# EMG.net
KiCad netlist of a schematic drawn in Altium Designer
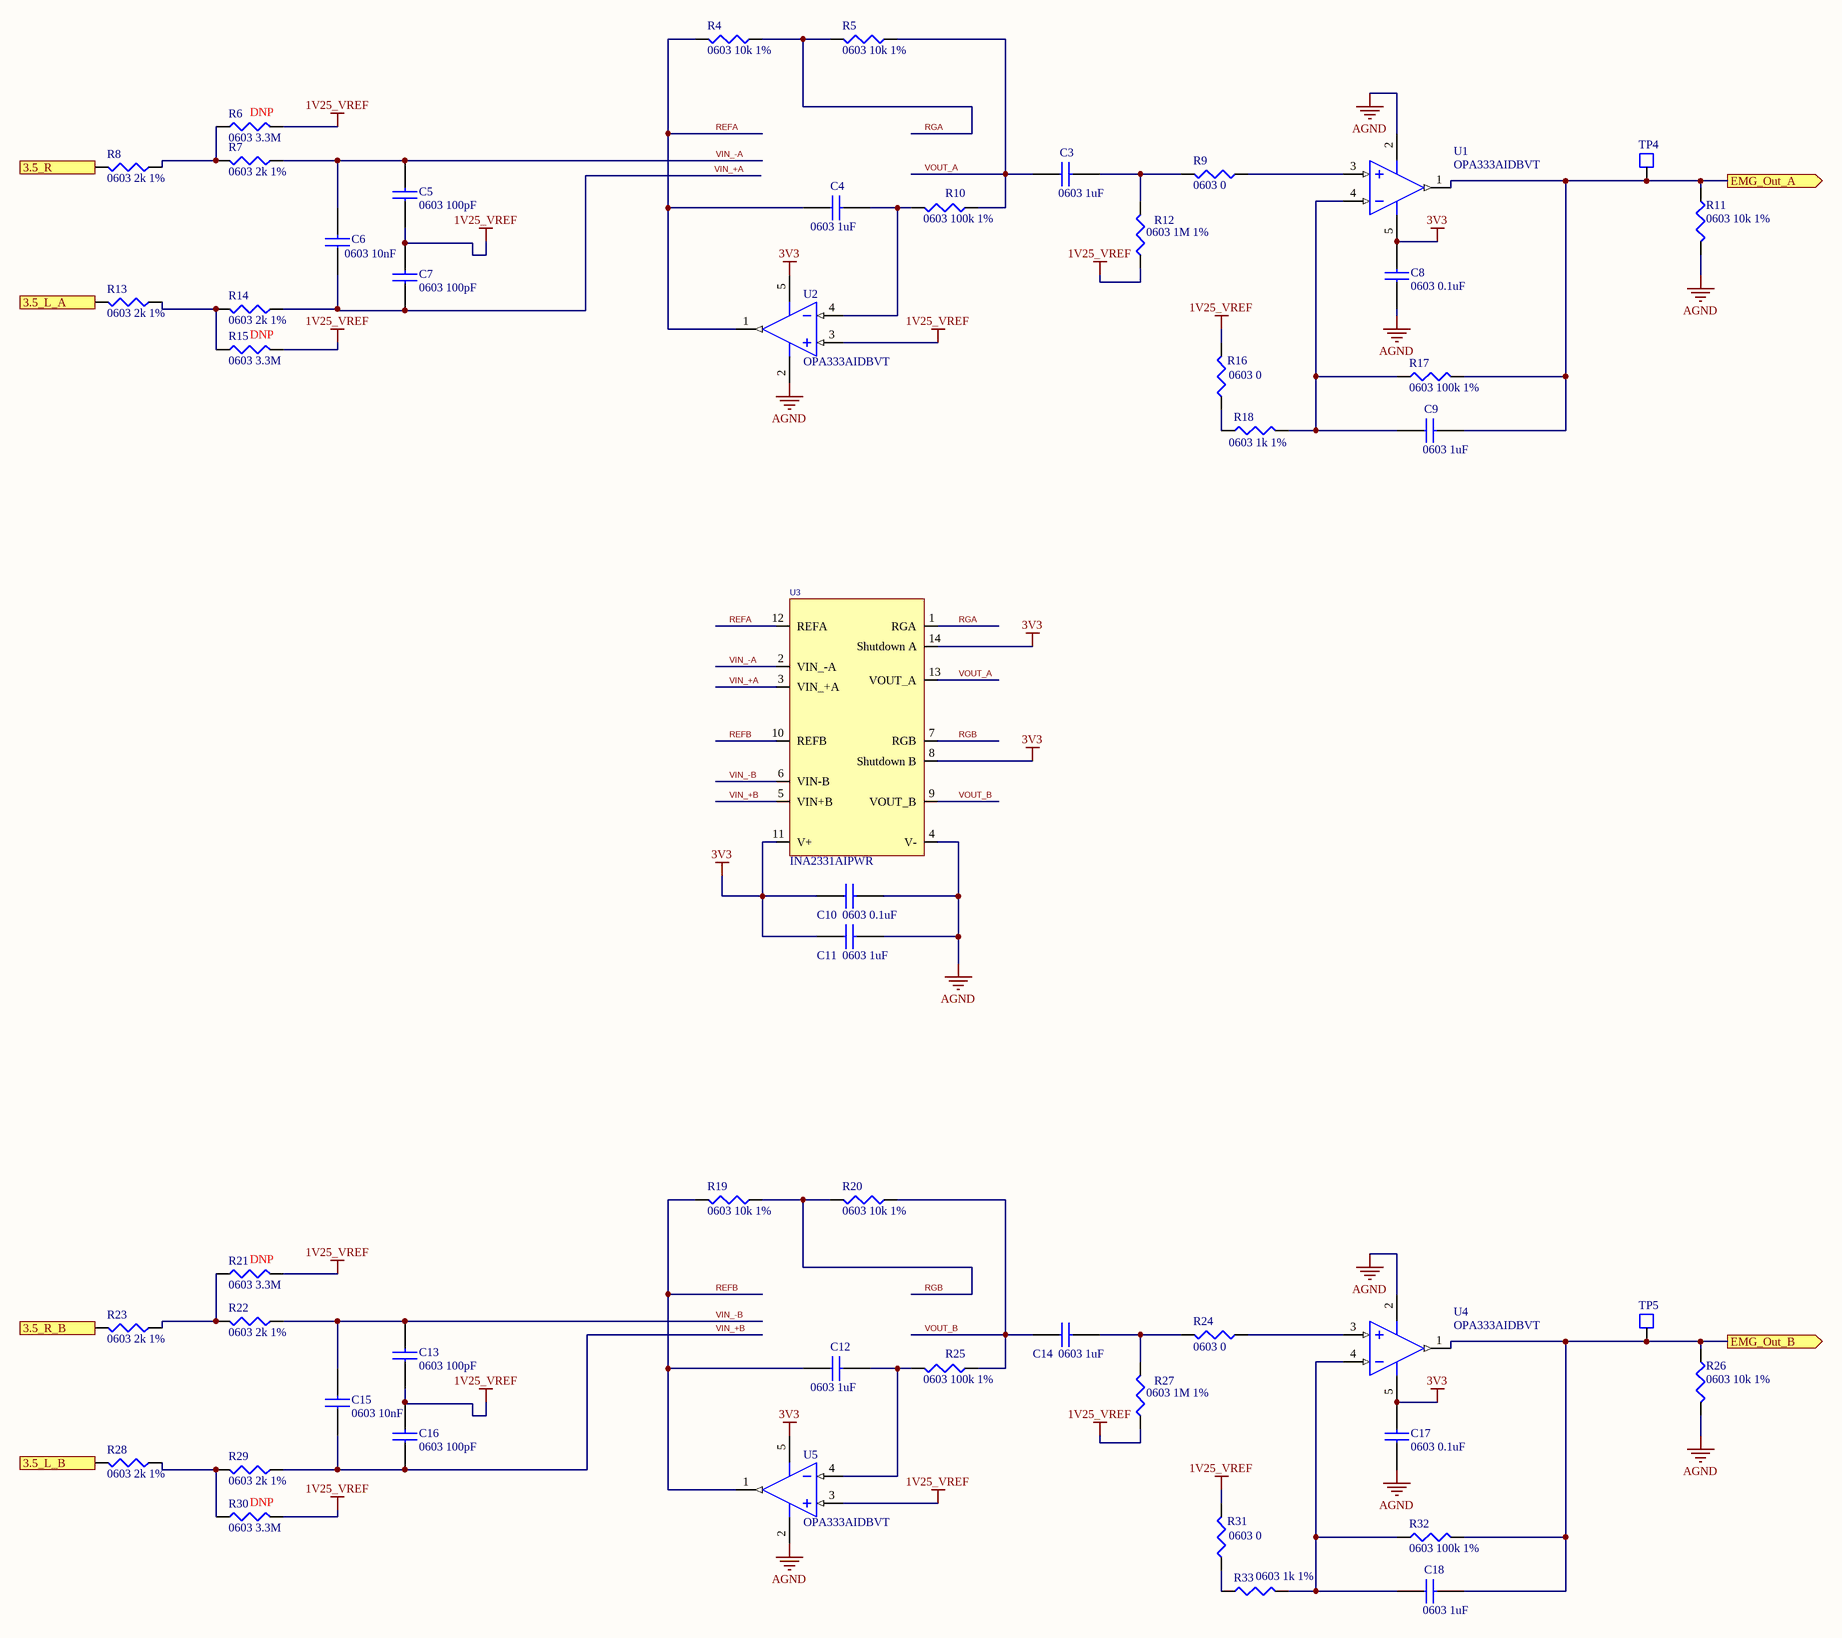
[diagram p0: EMG.SchDoc]

(export (version "E")
  (design (tool "Eeschema 10.0.6"))
  (components
    (comp (ref "C3")
      (value "0603 1uF")
      (footprint "CAP_0603_CER")
      (description "Generic Cap for NC (No Polar)\r\nESR <30mOhm\r\nESL <1.5nH,\r\nX5R")
      (fields
        (field (name "MANUFACTURER") "KEMET")
        (field (name "MANUFACTURER PART NUMBER") "C0603C105K8RAC7867")
      )
      (libsource (lib "BioSens") (part "CAP_NP"))
    )
    (comp (ref "C4")
      (value "0603 1uF")
      (footprint "CAP_0603_CER")
      (description "Generic Cap for NC (No Polar)\r\nESR <30mOhm\r\nESL <1.5nH,\r\nX5R")
      (fields
        (field (name "MANUFACTURER") "KEMET")
        (field (name "MANUFACTURER PART NUMBER") "C0603C105K8RAC7867")
      )
      (libsource (lib "BioSens") (part "CAP_NP"))
    )
    (comp (ref "C5")
      (value "0603 100pF")
      (footprint "CAP_0603_CER")
      (description "Generic Cap for NC (No Polar)\r\nESR <30mOhm\r\nESL <1.5nH,\r\nC0G")
      (fields
        (field (name "MANUFACTURER") "KEMET")
        (field (name "MANUFACTURER PART NUMBER") "C0603C101J3GAC7867")
      )
      (libsource (lib "BioSens") (part "CAP_NP"))
    )
    (comp (ref "C6")
      (value "0603 10nF")
      (footprint "CAP_0603_CER")
      (description "Generic Cap for NC (No Polar)\r\nESR <30mOhm\r\nESL <1.5nH,\r\nX7R")
      (fields
        (field (name "MANUFACTURER") "KEMET")
        (field (name "MANUFACTURER PART NUMBER") "C0603C103K4REC7867")
      )
      (libsource (lib "BioSens") (part "CAP_NP"))
    )
    (comp (ref "C7")
      (value "0603 100pF")
      (footprint "CAP_0603_CER")
      (description "Generic Cap for NC (No Polar)\r\nESR <30mOhm\r\nESL <1.5nH,\r\nC0G")
      (fields
        (field (name "MANUFACTURER") "KEMET")
        (field (name "MANUFACTURER PART NUMBER") "C0603C101J3GAC7867")
      )
      (libsource (lib "BioSens") (part "CAP_NP"))
    )
    (comp (ref "C8")
      (value "0603 0.1uF")
      (footprint "CAP_0603_CER")
      (description "Generic Cap for NC (No Polar)\r\nESR <30mOhm\r\nESL <1.5nH,\r\nX7R")
      (fields
        (field (name "MANUFACTURER") "KEMET")
        (field (name "MANUFACTURER PART NUMBER") "C0603C104K5RAC7867")
      )
      (libsource (lib "BioSens") (part "CAP_NP"))
    )
    (comp (ref "C9")
      (value "0603 1uF")
      (footprint "CAP_0603_CER")
      (description "Generic Cap for NC (No Polar)\r\nESR <30mOhm\r\nESL <1.5nH,\r\nX7R")
      (fields
        (field (name "MANUFACTURER") "KEMET")
        (field (name "MANUFACTURER PART NUMBER") "C0603C105K8RAC7867")
      )
      (libsource (lib "BioSens") (part "CAP_NP"))
    )
    (comp (ref "C10")
      (value "0603 0.1uF")
      (footprint "CAP_0603_CER")
      (description "Generic Cap for NC (No Polar)\r\nESR <30mOhm\r\nESL <1.5nH,\r\nX7R")
      (fields
        (field (name "MANUFACTURER") "KEMET")
        (field (name "MANUFACTURER PART NUMBER") "C0603C104K5RAC7867")
      )
      (libsource (lib "BioSens") (part "CAP_NP"))
    )
    (comp (ref "C11")
      (value "0603 1uF")
      (footprint "CAP_0603_CER")
      (description "Generic Cap for NC (No Polar)\r\nESR <30mOhm\r\nESL <1.5nH,\r\nX5R")
      (fields
        (field (name "MANUFACTURER") "KEMET")
        (field (name "MANUFACTURER PART NUMBER") "C0603C105K8RAC7867")
      )
      (libsource (lib "BioSens") (part "CAP_NP"))
    )
    (comp (ref "C12")
      (value "0603 1uF")
      (footprint "CAP_0603_CER")
      (description "Generic Cap for NC (No Polar)\r\nESR <30mOhm\r\nESL <1.5nH,\r\nX5R")
      (fields
        (field (name "MANUFACTURER") "KEMET")
        (field (name "MANUFACTURER PART NUMBER") "C0603C105K8RAC7867")
      )
      (libsource (lib "BioSens") (part "CAP_NP"))
    )
    (comp (ref "C13")
      (value "0603 100pF")
      (footprint "CAP_0603_CER")
      (description "Generic Cap for NC (No Polar)\r\nESR <30mOhm\r\nESL <1.5nH,\r\nC0G")
      (fields
        (field (name "MANUFACTURER") "KEMET")
        (field (name "MANUFACTURER PART NUMBER") "C0603C101J3GAC7867")
      )
      (libsource (lib "BioSens") (part "CAP_NP"))
    )
    (comp (ref "C14")
      (value "0603 1uF")
      (footprint "CAP_0603_CER")
      (description "Generic Cap for NC (No Polar)\r\nESR <30mOhm\r\nESL <1.5nH,\r\nX5R")
      (fields
        (field (name "MANUFACTURER") "KEMET")
        (field (name "MANUFACTURER PART NUMBER") "C0603C105K8RAC7867")
      )
      (libsource (lib "BioSens") (part "CAP_NP"))
    )
    (comp (ref "C15")
      (value "0603 10nF")
      (footprint "CAP_0603_CER")
      (description "Generic Cap for NC (No Polar)\r\nESR <30mOhm\r\nESL <1.5nH,\r\nX7R")
      (fields
        (field (name "MANUFACTURER") "KEMET")
        (field (name "MANUFACTURER PART NUMBER") "C0603C103K4REC7867")
      )
      (libsource (lib "BioSens") (part "CAP_NP"))
    )
    (comp (ref "C16")
      (value "0603 100pF")
      (footprint "CAP_0603_CER")
      (description "Generic Cap for NC (No Polar)\r\nESR <30mOhm\r\nESL <1.5nH,\r\nC0G")
      (fields
        (field (name "MANUFACTURER") "KEMET")
        (field (name "MANUFACTURER PART NUMBER") "C0603C101J3GAC7867")
      )
      (libsource (lib "BioSens") (part "CAP_NP"))
    )
    (comp (ref "C17")
      (value "0603 0.1uF")
      (footprint "CAP_0603_CER")
      (description "Generic Cap for NC (No Polar)\r\nESR <30mOhm\r\nESL <1.5nH,\r\nX7R")
      (fields
        (field (name "MANUFACTURER") "KEMET")
        (field (name "MANUFACTURER PART NUMBER") "C0603C104K5RAC7867")
      )
      (libsource (lib "BioSens") (part "CAP_NP"))
    )
    (comp (ref "C18")
      (value "0603 1uF")
      (footprint "CAP_0603_CER")
      (description "Generic Cap for NC (No Polar)\r\nESR <30mOhm\r\nESL <1.5nH,\r\nX7R")
      (fields
        (field (name "MANUFACTURER") "KEMET")
        (field (name "MANUFACTURER PART NUMBER") "C0603C105K8RAC7867")
      )
      (libsource (lib "BioSens") (part "CAP_NP"))
    )
    (comp (ref "R4")
      (value "0603 10k 1%")
      (footprint "0603")
      (description "Generic Resistor")
      (fields (field (name "MANUFACTURER") "YAGEO"))
      (libsource (lib "BioSens") (part "RESISTOR"))
    )
    (comp (ref "R5")
      (value "0603 10k 1%")
      (footprint "0603")
      (description "Generic Resistor")
      (fields (field (name "MANUFACTURER") "YAGEO"))
      (libsource (lib "BioSens") (part "RESISTOR"))
    )
    (comp (ref "R6")
      (value "0603 3.3M")
      (footprint "0603")
      (description "Generic Resistor")
      (libsource (lib "BioSens") (part "RESISTOR"))
    )
    (comp (ref "R7")
      (value "0603 2k 1%")
      (footprint "0603")
      (description "Generic Resistor")
      (fields (field (name "MANUFACTURER") "YAGEO"))
      (libsource (lib "BioSens") (part "RESISTOR"))
    )
    (comp (ref "R8")
      (value "0603 2k 1%")
      (footprint "0603")
      (description "Generic Resistor")
      (fields (field (name "MANUFACTURER") "YAGEO"))
      (libsource (lib "BioSens") (part "RESISTOR"))
    )
    (comp (ref "R9")
      (value "0603 0")
      (footprint "0603")
      (description "Generic Resistor")
      (fields (field (name "MANUFACTURER") "YAGEO"))
      (libsource (lib "BioSens") (part "RESISTOR"))
    )
    (comp (ref "R10")
      (value "0603 100k 1%")
      (footprint "0603")
      (description "Generic Resistor")
      (fields (field (name "MANUFACTURER") "Vishay Dale"))
      (libsource (lib "BioSens") (part "RESISTOR"))
    )
    (comp (ref "R11")
      (value "0603 10k 1%")
      (footprint "0603")
      (description "Generic Resistor")
      (fields (field (name "MANUFACTURER") "YAGEO"))
      (libsource (lib "BioSens") (part "RESISTOR"))
    )
    (comp (ref "R12")
      (value "0603 1M 1%")
      (footprint "0603")
      (description "Generic Resistor")
      (libsource (lib "BioSens") (part "RESISTOR"))
    )
    (comp (ref "R13")
      (value "0603 2k 1%")
      (footprint "0603")
      (description "Generic Resistor")
      (fields (field (name "MANUFACTURER") "YAGEO"))
      (libsource (lib "BioSens") (part "RESISTOR"))
    )
    (comp (ref "R14")
      (value "0603 2k 1%")
      (footprint "0603")
      (description "Generic Resistor")
      (fields (field (name "MANUFACTURER") "YAGEO"))
      (libsource (lib "BioSens") (part "RESISTOR"))
    )
    (comp (ref "R15")
      (value "0603 3.3M")
      (footprint "0603")
      (description "Generic Resistor")
      (libsource (lib "BioSens") (part "RESISTOR"))
    )
    (comp (ref "R16")
      (value "0603 0")
      (footprint "0603")
      (description "Generic Resistor")
      (fields (field (name "MANUFACTURER") "YAGEO"))
      (libsource (lib "BioSens") (part "RESISTOR"))
    )
    (comp (ref "R17")
      (value "0603 100k 1%")
      (footprint "0603")
      (description "Generic Resistor")
      (fields (field (name "MANUFACTURER") "Vishay Dale"))
      (libsource (lib "BioSens") (part "RESISTOR"))
    )
    (comp (ref "R18")
      (value "0603 1k 1%")
      (footprint "0603")
      (description "Generic Resistor")
      (fields (field (name "MANUFACTURER") "Vishay Dale"))
      (libsource (lib "BioSens") (part "RESISTOR"))
    )
    (comp (ref "R19")
      (value "0603 10k 1%")
      (footprint "0603")
      (description "Generic Resistor")
      (fields (field (name "MANUFACTURER") "YAGEO"))
      (libsource (lib "BioSens") (part "RESISTOR"))
    )
    (comp (ref "R20")
      (value "0603 10k 1%")
      (footprint "0603")
      (description "Generic Resistor")
      (fields (field (name "MANUFACTURER") "YAGEO"))
      (libsource (lib "BioSens") (part "RESISTOR"))
    )
    (comp (ref "R21")
      (value "0603 3.3M")
      (footprint "0603")
      (description "Generic Resistor")
      (libsource (lib "BioSens") (part "RESISTOR"))
    )
    (comp (ref "R22")
      (value "0603 2k 1%")
      (footprint "0603")
      (description "Generic Resistor")
      (fields (field (name "MANUFACTURER") "YAGEO"))
      (libsource (lib "BioSens") (part "RESISTOR"))
    )
    (comp (ref "R23")
      (value "0603 2k 1%")
      (footprint "0603")
      (description "Generic Resistor")
      (fields (field (name "MANUFACTURER") "YAGEO"))
      (libsource (lib "BioSens") (part "RESISTOR"))
    )
    (comp (ref "R24")
      (value "0603 0")
      (footprint "0603")
      (description "Generic Resistor")
      (fields (field (name "MANUFACTURER") "YAGEO"))
      (libsource (lib "BioSens") (part "RESISTOR"))
    )
    (comp (ref "R25")
      (value "0603 100k 1%")
      (footprint "0603")
      (description "Generic Resistor")
      (fields (field (name "MANUFACTURER") "Vishay Dale"))
      (libsource (lib "BioSens") (part "RESISTOR"))
    )
    (comp (ref "R26")
      (value "0603 10k 1%")
      (footprint "0603")
      (description "Generic Resistor")
      (fields (field (name "MANUFACTURER") "YAGEO"))
      (libsource (lib "BioSens") (part "RESISTOR"))
    )
    (comp (ref "R27")
      (value "0603 1M 1%")
      (footprint "0603")
      (description "Generic Resistor")
      (libsource (lib "BioSens") (part "RESISTOR"))
    )
    (comp (ref "R28")
      (value "0603 2k 1%")
      (footprint "0603")
      (description "Generic Resistor")
      (fields (field (name "MANUFACTURER") "YAGEO"))
      (libsource (lib "BioSens") (part "RESISTOR"))
    )
    (comp (ref "R29")
      (value "0603 2k 1%")
      (footprint "0603")
      (description "Generic Resistor")
      (fields (field (name "MANUFACTURER") "YAGEO"))
      (libsource (lib "BioSens") (part "RESISTOR"))
    )
    (comp (ref "R30")
      (value "0603 3.3M")
      (footprint "0603")
      (description "Generic Resistor")
      (libsource (lib "BioSens") (part "RESISTOR"))
    )
    (comp (ref "R31")
      (value "0603 0")
      (footprint "0603")
      (description "Generic Resistor")
      (fields (field (name "MANUFACTURER") "YAGEO"))
      (libsource (lib "BioSens") (part "RESISTOR"))
    )
    (comp (ref "R32")
      (value "0603 100k 1%")
      (footprint "0603")
      (description "Generic Resistor")
      (fields (field (name "MANUFACTURER") "Vishay Dale"))
      (libsource (lib "BioSens") (part "RESISTOR"))
    )
    (comp (ref "R33")
      (value "0603 1k 1%")
      (footprint "0603")
      (description "Generic Resistor")
      (fields (field (name "MANUFACTURER") "Vishay Dale"))
      (libsource (lib "BioSens") (part "RESISTOR"))
    )
    (comp (ref "TP4")
      (value "0402_TEST_PT")
      (footprint "0402_PAD")
      (libsource (lib "BioSens") (part "0402_TEST_PT"))
    )
    (comp (ref "TP5")
      (value "0402_TEST_PT")
      (footprint "0402_PAD")
      (libsource (lib "BioSens") (part "0402_TEST_PT"))
    )
    (comp (ref "U1")
      (value "OPA333AIDBVT")
      (footprint "DBV0005A_M")
      (fields (field (name "MANUFACTURER") "Texas Instruments (TI)"))
      (libsource (lib "University of California Berkeley") (part "TI-OPA333DBV5"))
    )
    (comp (ref "U2")
      (value "OPA333AIDBVT")
      (footprint "DBV0005A_M")
      (fields (field (name "MANUFACTURER") "Texas Instruments (TI)"))
      (libsource (lib "University of California Berkeley") (part "TI-OPA333DBV5"))
    )
    (comp (ref "U3")
      (value "INA2331AIPWR")
      (footprint "TSOP65P640X120-14N")
      (description "Low-power, single-supply, CMOS, instrumentation amplifier 14-TSSOP -55 to 125")
      (fields (field (name "MANUFACTURER") "Texas Instruments"))
      (libsource (lib "BioSens") (part "INA2331AIPWR"))
    )
    (comp (ref "U4")
      (value "OPA333AIDBVT")
      (footprint "DBV0005A_M")
      (fields (field (name "MANUFACTURER") "Texas Instruments (TI)"))
      (libsource (lib "University of California Berkeley") (part "TI-OPA333DBV5"))
    )
    (comp (ref "U5")
      (value "OPA333AIDBVT")
      (footprint "DBV0005A_M")
      (fields (field (name "MANUFACTURER") "Texas Instruments (TI)"))
      (libsource (lib "University of California Berkeley") (part "TI-OPA333DBV5"))
    )
  )
  (nets
    (net (code "1") (name "/3.5_L_A") (class "Default")
      (node (ref "R13") (pin "2") (pinfunction "2_2") (pintype "passive"))
    )
    (net (code "2") (name "/3.5_L_B") (class "Default")
      (node (ref "R28") (pin "2") (pinfunction "2_2") (pintype "passive"))
    )
    (net (code "3") (name "/3.5_R") (class "Default")
      (node (ref "R8") (pin "2") (pinfunction "2_2") (pintype "passive"))
    )
    (net (code "4") (name "/3.5_R_B") (class "Default")
      (node (ref "R23") (pin "2") (pinfunction "2_2") (pintype "passive"))
    )
    (net (code "5") (name "/EMG_Out_A") (class "Default")
      (node (ref "C9") (pin "2") (pinfunction "2_2") (pintype "passive"))
      (node (ref "R11") (pin "1") (pinfunction "1_1") (pintype "passive"))
      (node (ref "R17") (pin "2") (pinfunction "2_2") (pintype "passive"))
      (node (ref "TP4") (pin "1") (pintype "passive"))
      (node (ref "U1") (pin "1") (pinfunction "OUT_1") (pintype "output"))
    )
    (net (code "6") (name "/EMG_Out_B") (class "Default")
      (node (ref "C18") (pin "2") (pinfunction "2_2") (pintype "passive"))
      (node (ref "R26") (pin "1") (pinfunction "1_1") (pintype "passive"))
      (node (ref "R32") (pin "2") (pinfunction "2_2") (pintype "passive"))
      (node (ref "TP5") (pin "1") (pintype "passive"))
      (node (ref "U4") (pin "1") (pinfunction "OUT_1") (pintype "output"))
    )
    (net (code "7") (name "/REFA") (class "Default")
      (node (ref "C4") (pin "1") (pinfunction "1_1") (pintype "passive"))
      (node (ref "R4") (pin "2") (pinfunction "2_2") (pintype "passive"))
      (node (ref "U2") (pin "1") (pinfunction "OUT_1") (pintype "output"))
      (node (ref "U3") (pin "12") (pinfunction "REFA_12") (pintype "passive"))
    )
    (net (code "8") (name "/REFB") (class "Default")
      (node (ref "C12") (pin "1") (pinfunction "1_1") (pintype "passive"))
      (node (ref "R19") (pin "2") (pinfunction "2_2") (pintype "passive"))
      (node (ref "U3") (pin "10") (pinfunction "REFB_10") (pintype "passive"))
      (node (ref "U5") (pin "1") (pinfunction "OUT_1") (pintype "output"))
    )
    (net (code "9") (name "/RGA") (class "Default")
      (node (ref "R4") (pin "1") (pinfunction "1_1") (pintype "passive"))
      (node (ref "R5") (pin "2") (pinfunction "2_2") (pintype "passive"))
      (node (ref "U3") (pin "1") (pinfunction "RGA_1") (pintype "passive"))
    )
    (net (code "10") (name "/RGB") (class "Default")
      (node (ref "R19") (pin "1") (pinfunction "1_1") (pintype "passive"))
      (node (ref "R20") (pin "2") (pinfunction "2_2") (pintype "passive"))
      (node (ref "U3") (pin "7") (pinfunction "RGB_7") (pintype "passive"))
    )
    (net (code "11") (name "/VIN_+A") (class "Default")
      (node (ref "C6") (pin "1") (pinfunction "1_1") (pintype "passive"))
      (node (ref "C7") (pin "1") (pinfunction "1_1") (pintype "passive"))
      (node (ref "R14") (pin "1") (pinfunction "1_1") (pintype "passive"))
      (node (ref "U3") (pin "3") (pinfunction "VIN_+A_3") (pintype "passive"))
    )
    (net (code "12") (name "/VIN_+B") (class "Default")
      (node (ref "C15") (pin "1") (pinfunction "1_1") (pintype "passive"))
      (node (ref "C16") (pin "1") (pinfunction "1_1") (pintype "passive"))
      (node (ref "R29") (pin "1") (pinfunction "1_1") (pintype "passive"))
      (node (ref "U3") (pin "5") (pinfunction "VIN+B_5") (pintype "passive"))
    )
    (net (code "13") (name "/VIN_-A") (class "Default")
      (node (ref "C5") (pin "2") (pinfunction "2_2") (pintype "passive"))
      (node (ref "C6") (pin "2") (pinfunction "2_2") (pintype "passive"))
      (node (ref "R7") (pin "1") (pinfunction "1_1") (pintype "passive"))
      (node (ref "U3") (pin "2") (pinfunction "VIN_-A_2") (pintype "passive"))
    )
    (net (code "14") (name "/VIN_-B") (class "Default")
      (node (ref "C13") (pin "2") (pinfunction "2_2") (pintype "passive"))
      (node (ref "C15") (pin "2") (pinfunction "2_2") (pintype "passive"))
      (node (ref "R22") (pin "1") (pinfunction "1_1") (pintype "passive"))
      (node (ref "U3") (pin "6") (pinfunction "VIN-B_6") (pintype "passive"))
    )
    (net (code "15") (name "/VOUT_A") (class "Default")
      (node (ref "C3") (pin "1") (pinfunction "1_1") (pintype "passive"))
      (node (ref "R10") (pin "1") (pinfunction "1_1") (pintype "passive"))
      (node (ref "R5") (pin "1") (pinfunction "1_1") (pintype "passive"))
      (node (ref "U3") (pin "13") (pinfunction "VOUT_A_13") (pintype "passive"))
    )
    (net (code "16") (name "/VOUT_B") (class "Default")
      (node (ref "C14") (pin "1") (pinfunction "1_1") (pintype "passive"))
      (node (ref "R20") (pin "1") (pinfunction "1_1") (pintype "passive"))
      (node (ref "R25") (pin "1") (pinfunction "1_1") (pintype "passive"))
      (node (ref "U3") (pin "9") (pinfunction "VOUT_B_9") (pintype "passive"))
    )
    (net (code "17") (name "1V25_VREF") (class "Default")
      (node (ref "C13") (pin "1") (pinfunction "1_1") (pintype "passive"))
      (node (ref "C16") (pin "2") (pinfunction "2_2") (pintype "passive"))
      (node (ref "C5") (pin "1") (pinfunction "1_1") (pintype "passive"))
      (node (ref "C7") (pin "2") (pinfunction "2_2") (pintype "passive"))
      (node (ref "R12") (pin "1") (pinfunction "1_1") (pintype "passive"))
      (node (ref "R15") (pin "2") (pinfunction "2_2") (pintype "passive"))
      (node (ref "R16") (pin "2") (pinfunction "2_2") (pintype "passive"))
      (node (ref "R21") (pin "2") (pinfunction "2_2") (pintype "passive"))
      (node (ref "R27") (pin "1") (pinfunction "1_1") (pintype "passive"))
      (node (ref "R30") (pin "2") (pinfunction "2_2") (pintype "passive"))
      (node (ref "R31") (pin "2") (pinfunction "2_2") (pintype "passive"))
      (node (ref "R6") (pin "2") (pinfunction "2_2") (pintype "passive"))
      (node (ref "U2") (pin "3") (pinfunction "+IN_3") (pintype "input"))
      (node (ref "U5") (pin "3") (pinfunction "+IN_3") (pintype "input"))
    )
    (net (code "18") (name "3V3") (class "Default")
      (node (ref "C10") (pin "1") (pinfunction "1_1") (pintype "passive"))
      (node (ref "C11") (pin "1") (pinfunction "1_1") (pintype "passive"))
      (node (ref "C17") (pin "2") (pinfunction "2_2") (pintype "passive"))
      (node (ref "C8") (pin "2") (pinfunction "2_2") (pintype "passive"))
      (node (ref "U1") (pin "5") (pinfunction "V+_5") (pintype "power_in"))
      (node (ref "U2") (pin "5") (pinfunction "V+_5") (pintype "power_in"))
      (node (ref "U3") (pin "11") (pinfunction "V+_11") (pintype "passive"))
      (node (ref "U3") (pin "14") (pinfunction "Shutdown_A_14") (pintype "passive"))
      (node (ref "U3") (pin "8") (pinfunction "Shutdown_B_8") (pintype "passive"))
      (node (ref "U4") (pin "5") (pinfunction "V+_5") (pintype "power_in"))
      (node (ref "U5") (pin "5") (pinfunction "V+_5") (pintype "power_in"))
    )
    (net (code "19") (name "AGND") (class "Default")
      (node (ref "C10") (pin "2") (pinfunction "2_2") (pintype "passive"))
      (node (ref "C11") (pin "2") (pinfunction "2_2") (pintype "passive"))
      (node (ref "C17") (pin "1") (pinfunction "1_1") (pintype "passive"))
      (node (ref "C8") (pin "1") (pinfunction "1_1") (pintype "passive"))
      (node (ref "R11") (pin "2") (pinfunction "2_2") (pintype "passive"))
      (node (ref "R26") (pin "2") (pinfunction "2_2") (pintype "passive"))
      (node (ref "U1") (pin "2") (pinfunction "V-_2") (pintype "power_in"))
      (node (ref "U2") (pin "2") (pinfunction "V-_2") (pintype "power_in"))
      (node (ref "U3") (pin "4") (pinfunction "V-_4") (pintype "passive"))
      (node (ref "U4") (pin "2") (pinfunction "V-_2") (pintype "power_in"))
      (node (ref "U5") (pin "2") (pinfunction "V-_2") (pintype "power_in"))
    )
    (net (code "20") (name "Net-(C3-Pad2)") (class "Default")
      (node (ref "C3") (pin "2") (pinfunction "2_2") (pintype "passive"))
      (node (ref "R12") (pin "2") (pinfunction "2_2") (pintype "passive"))
      (node (ref "R9") (pin "2") (pinfunction "2_2") (pintype "passive"))
    )
    (net (code "21") (name "Net-(C14-Pad2)") (class "Default")
      (node (ref "C14") (pin "2") (pinfunction "2_2") (pintype "passive"))
      (node (ref "R24") (pin "2") (pinfunction "2_2") (pintype "passive"))
      (node (ref "R27") (pin "2") (pinfunction "2_2") (pintype "passive"))
    )
    (net (code "22") (name "Net-(R6-Pad1)") (class "Default")
      (node (ref "R6") (pin "1") (pinfunction "1_1") (pintype "passive"))
      (node (ref "R7") (pin "2") (pinfunction "2_2") (pintype "passive"))
      (node (ref "R8") (pin "1") (pinfunction "1_1") (pintype "passive"))
    )
    (net (code "23") (name "Net-(R13-Pad1)") (class "Default")
      (node (ref "R13") (pin "1") (pinfunction "1_1") (pintype "passive"))
      (node (ref "R14") (pin "2") (pinfunction "2_2") (pintype "passive"))
      (node (ref "R15") (pin "1") (pinfunction "1_1") (pintype "passive"))
    )
    (net (code "24") (name "Net-(R16-Pad1)") (class "Default")
      (node (ref "R16") (pin "1") (pinfunction "1_1") (pintype "passive"))
      (node (ref "R18") (pin "1") (pinfunction "1_1") (pintype "passive"))
    )
    (net (code "25") (name "Net-(R21-Pad1)") (class "Default")
      (node (ref "R21") (pin "1") (pinfunction "1_1") (pintype "passive"))
      (node (ref "R22") (pin "2") (pinfunction "2_2") (pintype "passive"))
      (node (ref "R23") (pin "1") (pinfunction "1_1") (pintype "passive"))
    )
    (net (code "26") (name "Net-(R28-Pad1)") (class "Default")
      (node (ref "R28") (pin "1") (pinfunction "1_1") (pintype "passive"))
      (node (ref "R29") (pin "2") (pinfunction "2_2") (pintype "passive"))
      (node (ref "R30") (pin "1") (pinfunction "1_1") (pintype "passive"))
    )
    (net (code "27") (name "Net-(R31-Pad1)") (class "Default")
      (node (ref "R31") (pin "1") (pinfunction "1_1") (pintype "passive"))
      (node (ref "R33") (pin "1") (pinfunction "1_1") (pintype "passive"))
    )
    (net (code "28") (name "Net-(U1-+IN)") (class "Default")
      (node (ref "R9") (pin "1") (pinfunction "1_1") (pintype "passive"))
      (node (ref "U1") (pin "3") (pinfunction "+IN_3") (pintype "input"))
    )
    (net (code "29") (name "Net-(U1--IN)") (class "Default")
      (node (ref "C9") (pin "1") (pinfunction "1_1") (pintype "passive"))
      (node (ref "R17") (pin "1") (pinfunction "1_1") (pintype "passive"))
      (node (ref "R18") (pin "2") (pinfunction "2_2") (pintype "passive"))
      (node (ref "U1") (pin "4") (pinfunction "-IN_4") (pintype "input"))
    )
    (net (code "30") (name "Net-(U2--IN)") (class "Default")
      (node (ref "C4") (pin "2") (pinfunction "2_2") (pintype "passive"))
      (node (ref "R10") (pin "2") (pinfunction "2_2") (pintype "passive"))
      (node (ref "U2") (pin "4") (pinfunction "-IN_4") (pintype "input"))
    )
    (net (code "31") (name "Net-(U4-+IN)") (class "Default")
      (node (ref "R24") (pin "1") (pinfunction "1_1") (pintype "passive"))
      (node (ref "U4") (pin "3") (pinfunction "+IN_3") (pintype "input"))
    )
    (net (code "32") (name "Net-(U4--IN)") (class "Default")
      (node (ref "C18") (pin "1") (pinfunction "1_1") (pintype "passive"))
      (node (ref "R32") (pin "1") (pinfunction "1_1") (pintype "passive"))
      (node (ref "R33") (pin "2") (pinfunction "2_2") (pintype "passive"))
      (node (ref "U4") (pin "4") (pinfunction "-IN_4") (pintype "input"))
    )
    (net (code "33") (name "Net-(U5--IN)") (class "Default")
      (node (ref "C12") (pin "2") (pinfunction "2_2") (pintype "passive"))
      (node (ref "R25") (pin "2") (pinfunction "2_2") (pintype "passive"))
      (node (ref "U5") (pin "4") (pinfunction "-IN_4") (pintype "input"))
    )
  )
)
